# SCH_Mirge_Driving_Circuit_and_Power_2022.net
KiCad netlist of a schematic drawn in EasyEDA
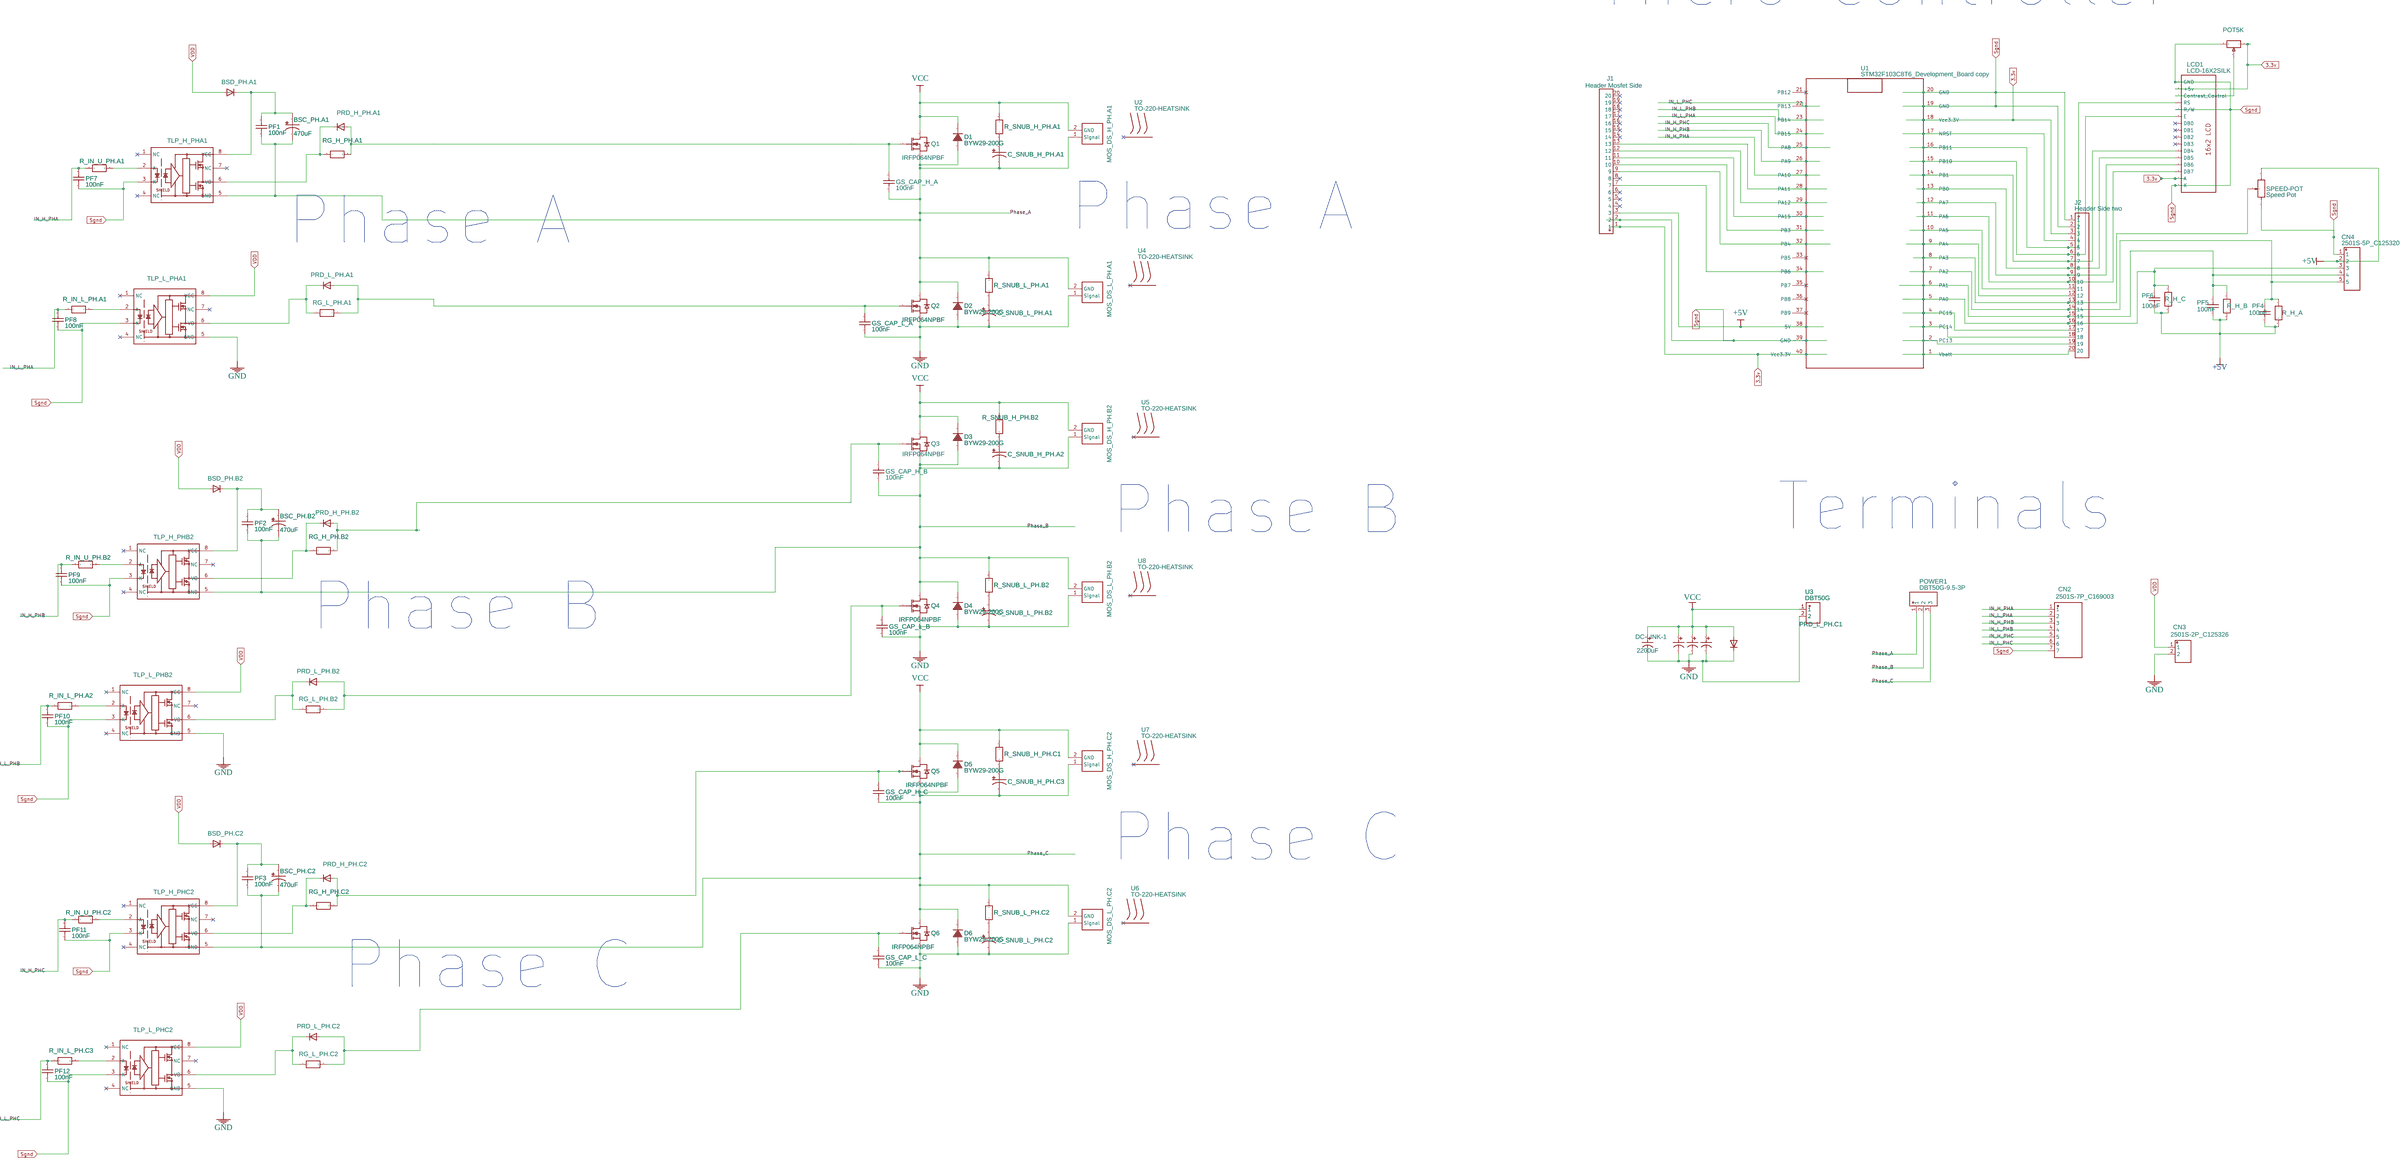
[diagram p0: schematic sheet]

(export (version "E")
  (design (tool "Eeschema 10.0.6"))
  (components
    (comp (ref "BSC_PH.A1")
      (value "470uF")
      (fields
        (field (name "BOM_Manufacturer Part") "RD1E477M1012MPA18P")
        (field (name "BOM_Supplier Part") "C160623")
      )
      (libsource (lib "") (part "RD1E477M1012MPA18P_4"))
    )
    (comp (ref "BSC_PH.B2")
      (value "470uF")
      (fields
        (field (name "BOM_Manufacturer Part") "RD1E477M1012MPA18P")
        (field (name "BOM_Supplier Part") "C160623")
      )
      (libsource (lib "") (part "RD1E477M1012MPA18P_2"))
    )
    (comp (ref "BSC_PH.C2")
      (value "470uF")
      (fields
        (field (name "BOM_Manufacturer Part") "RD1E477M1012MPA18P")
        (field (name "BOM_Supplier Part") "C160623")
      )
      (libsource (lib "") (part "RD1E477M1012MPA18P_3"))
    )
    (comp (ref "BSD_PH.A1") (value "DIODEDO-1N4148") (libsource (lib "") (part "DIODEDO-1N4148_2")))
    (comp (ref "BSD_PH.B2") (value "DIODEDO-1N4148") (libsource (lib "") (part "DIODEDO-1N4148_1")))
    (comp (ref "BSD_PH.C2") (value "DIODEDO-1N4148") (libsource (lib "") (part "DIODEDO-1N4148")))
    (comp (ref "CN2")
      (value "2501S-7P_C169003")
      (fields (field (name "BOM_Supplier Part") "C169003"))
      (libsource (lib "") (part "2501S-7P_C169003"))
    )
    (comp (ref "CN3")
      (value "2501S-2P_C125326")
      (fields (field (name "BOM_Manufacturer Part") "2501S-2P") (field (name "BOM_Supplier Part") "C125326"))
      (libsource (lib "") (part "2501S-2P_C125326"))
    )
    (comp (ref "CN4")
      (value "2501S-5P_C125320")
      (fields (field (name "BOM_Manufacturer Part") "2501S-5P") (field (name "BOM_Supplier Part") "C125320"))
      (libsource (lib "") (part "2501S-5P_C125320"))
    )
    (comp (ref "C_SNUB_H_PH.A1")
      (value "470uF")
      (fields
        (field (name "BOM_Manufacturer Part") "RD1E477M1012MPA18P")
        (field (name "BOM_Supplier Part") "C160623")
      )
      (libsource (lib "") (part "RD1E477M1012MPA18P_6"))
    )
    (comp (ref "C_SNUB_H_PH.A2")
      (value "470uF")
      (fields
        (field (name "BOM_Manufacturer Part") "RD1E477M1012MPA18P")
        (field (name "BOM_Supplier Part") "C160623")
      )
      (libsource (lib "") (part "RD1E477M1012MPA18P_1"))
    )
    (comp (ref "C_SNUB_H_PH.C3")
      (value "470uF")
      (fields
        (field (name "BOM_Manufacturer Part") "RD1E477M1012MPA18P")
        (field (name "BOM_Supplier Part") "C160623")
      )
      (libsource (lib "") (part "RD1E477M1012MPA18P"))
    )
    (comp (ref "C_SNUB_L_PH.A1")
      (value "470uF")
      (fields
        (field (name "BOM_Manufacturer Part") "RD1E477M1012MPA18P")
        (field (name "BOM_Supplier Part") "C160623")
      )
      (libsource (lib "") (part "RD1E477M1012MPA18P_8"))
    )
    (comp (ref "C_SNUB_L_PH.B2")
      (value "470uF")
      (fields
        (field (name "BOM_Manufacturer Part") "RD1E477M1012MPA18P")
        (field (name "BOM_Supplier Part") "C160623")
      )
      (libsource (lib "") (part "RD1E477M1012MPA18P_5"))
    )
    (comp (ref "C_SNUB_L_PH.C2")
      (value "470uF")
      (fields
        (field (name "BOM_Manufacturer Part") "RD1E477M1012MPA18P")
        (field (name "BOM_Supplier Part") "C160623")
      )
      (libsource (lib "") (part "RD1E477M1012MPA18P_7"))
    )
    (comp (ref "D1")
      (value "BYW29-200G")
      (fields (field (name "BOM_Supplier Part") "C232399"))
      (libsource (lib "") (part "BYW29-200G"))
    )
    (comp (ref "D2")
      (value "BYW29-200G")
      (fields (field (name "BOM_Supplier Part") "C232399"))
      (libsource (lib "") (part "BYW29-200G"))
    )
    (comp (ref "D3")
      (value "BYW29-200G")
      (fields (field (name "BOM_Supplier Part") "C232399"))
      (libsource (lib "") (part "BYW29-200G"))
    )
    (comp (ref "D4")
      (value "BYW29-200G")
      (fields (field (name "BOM_Supplier Part") "C232399"))
      (libsource (lib "") (part "BYW29-200G"))
    )
    (comp (ref "D5")
      (value "BYW29-200G")
      (fields (field (name "BOM_Supplier Part") "C232399"))
      (libsource (lib "") (part "BYW29-200G"))
    )
    (comp (ref "D6")
      (value "BYW29-200G")
      (fields (field (name "BOM_Supplier Part") "C232399"))
      (libsource (lib "") (part "BYW29-200G"))
    )
    (comp (ref "DC-LINK-1")
      (value "2200uF")
      (fields
        (field (name "BOM_Manufacturer Part") "2200uF 63V 18*30")
        (field (name "BOM_Supplier Part") "C47858")
      )
      (libsource (lib "") (part "2200uF 63V 18*30"))
    )
    (comp (ref "DC-LINK-2")
      (value "2200uF")
      (fields
        (field (name "BOM_Manufacturer Part") "2200uF 63V 18*30")
        (field (name "BOM_Supplier Part") "C47858")
      )
      (libsource (lib "") (part "2200uF 63V 18*30"))
    )
    (comp (ref "DC-LINK-3")
      (value "2200uF")
      (fields
        (field (name "BOM_Manufacturer Part") "2200uF 63V 18*30")
        (field (name "BOM_Supplier Part") "C47858")
      )
      (libsource (lib "") (part "2200uF 63V 18*30"))
    )
    (comp (ref "DC-LINK-4")
      (value "2200uF")
      (fields
        (field (name "BOM_Manufacturer Part") "2200uF 63V 18*30")
        (field (name "BOM_Supplier Part") "C47858")
      )
      (libsource (lib "") (part "2200uF 63V 18*30"))
    )
    (comp (ref "GS_CAP_H_A")
      (value "100nF")
      (fields
        (field (name "BOM_Manufacturer Part") "Calibration capacitor100nF（104）100V,5%")
        (field (name "BOM_Supplier Part") "C26609")
      )
      (libsource (lib "") (part "capacitor100nF（104）100V_3"))
    )
    (comp (ref "GS_CAP_H_B")
      (value "100nF")
      (fields
        (field (name "BOM_Manufacturer Part") "Calibration capacitor100nF（104）100V,5%")
        (field (name "BOM_Supplier Part") "C26609")
      )
      (libsource (lib "") (part "capacitor100nF（104）100V_4"))
    )
    (comp (ref "GS_CAP_H_C")
      (value "100nF")
      (fields
        (field (name "BOM_Manufacturer Part") "Calibration capacitor100nF（104）100V,5%")
        (field (name "BOM_Supplier Part") "C26609")
      )
      (libsource (lib "") (part "capacitor100nF（104）100V_7"))
    )
    (comp (ref "GS_CAP_L_A")
      (value "100nF")
      (fields
        (field (name "BOM_Manufacturer Part") "Calibration capacitor100nF（104）100V,5%")
        (field (name "BOM_Supplier Part") "C26609")
      )
      (libsource (lib "") (part "capacitor100nF（104）100V_2"))
    )
    (comp (ref "GS_CAP_L_B")
      (value "100nF")
      (fields
        (field (name "BOM_Manufacturer Part") "Calibration capacitor100nF（104）100V,5%")
        (field (name "BOM_Supplier Part") "C26609")
      )
      (libsource (lib "") (part "capacitor100nF（104）100V_6"))
    )
    (comp (ref "GS_CAP_L_C")
      (value "100nF")
      (fields
        (field (name "BOM_Manufacturer Part") "Calibration capacitor100nF（104）100V,5%")
        (field (name "BOM_Supplier Part") "C26609")
      )
      (libsource (lib "") (part "capacitor100nF（104）100V_5"))
    )
    (comp (ref "J1")
      (value "Header Mosfet Side")
      (fields
        (field (name "BOM_Manufacturer Part") "2.54mm 1*20PHeader")
        (field (name "BOM_Supplier Part") "C50981")
      )
      (libsource (lib "") (part "Header-Male-2.54_1x20_1"))
    )
    (comp (ref "J2")
      (value "Header Side two")
      (fields
        (field (name "BOM_Manufacturer Part") "2.54mm 1*20PHeader")
        (field (name "BOM_Supplier Part") "C50981")
      )
      (libsource (lib "") (part "Header-Male-2.54_1x20"))
    )
    (comp (ref "LCD1") (value "LCD-16X2SILK") (libsource (lib "") (part "LCD-16X2SILK")))
    (comp (ref "MOS_DS_H_PH.A1") (value "2 Pin Pinheader") (libsource (lib "") (part "2 Pin Pinheader_3")))
    (comp (ref "MOS_DS_H_PH.B2") (value "2 Pin Pinheader") (libsource (lib "") (part "2 Pin Pinheader_4")))
    (comp (ref "MOS_DS_H_PH.C2") (value "2 Pin Pinheader") (libsource (lib "") (part "2 Pin Pinheader")))
    (comp (ref "MOS_DS_L_PH.A1") (value "2 Pin Pinheader") (libsource (lib "") (part "2 Pin Pinheader_5")))
    (comp (ref "MOS_DS_L_PH.B2") (value "2 Pin Pinheader") (libsource (lib "") (part "2 Pin Pinheader_1")))
    (comp (ref "MOS_DS_L_PH.C2") (value "2 Pin Pinheader") (libsource (lib "") (part "2 Pin Pinheader_2")))
    (comp (ref "PF1")
      (value "100nF")
      (fields
        (field (name "BOM_Manufacturer Part") "Calibration capacitor100nF（104）100V,5%")
        (field (name "BOM_Supplier Part") "C26609")
      )
      (libsource (lib "") (part "capacitor100nF（104）100V_1"))
    )
    (comp (ref "PF2")
      (value "100nF")
      (fields
        (field (name "BOM_Manufacturer Part") "Calibration capacitor100nF（104）100V,5%")
        (field (name "BOM_Supplier Part") "C26609")
      )
      (libsource (lib "") (part "capacitor100nF（104）100V_1"))
    )
    (comp (ref "PF3")
      (value "100nF")
      (fields
        (field (name "BOM_Manufacturer Part") "Calibration capacitor100nF（104）100V,5%")
        (field (name "BOM_Supplier Part") "C26609")
      )
      (libsource (lib "") (part "capacitor100nF（104）100V_1"))
    )
    (comp (ref "PF4")
      (value "100nF")
      (fields
        (field (name "BOM_Manufacturer Part") "Calibration capacitor100nF（104）100V,5%")
        (field (name "BOM_Supplier Part") "C26609")
      )
      (libsource (lib "") (part "capacitor100nF（104）100V_1"))
    )
    (comp (ref "PF5")
      (value "100nF")
      (fields
        (field (name "BOM_Manufacturer Part") "Calibration capacitor100nF（104）100V,5%")
        (field (name "BOM_Supplier Part") "C26609")
      )
      (libsource (lib "") (part "capacitor100nF（104）100V"))
    )
    (comp (ref "PF6")
      (value "100nF")
      (fields
        (field (name "BOM_Manufacturer Part") "Calibration capacitor100nF（104）100V,5%")
        (field (name "BOM_Supplier Part") "C26609")
      )
      (libsource (lib "") (part "capacitor100nF（104）100V"))
    )
    (comp (ref "PF7")
      (value "100nF")
      (fields
        (field (name "BOM_Manufacturer Part") "Calibration capacitor100nF（104）100V,5%")
        (field (name "BOM_Supplier Part") "C26609")
      )
      (libsource (lib "") (part "capacitor100nF（104）100V_1"))
    )
    (comp (ref "PF8")
      (value "100nF")
      (fields
        (field (name "BOM_Manufacturer Part") "Calibration capacitor100nF（104）100V,5%")
        (field (name "BOM_Supplier Part") "C26609")
      )
      (libsource (lib "") (part "capacitor100nF（104）100V_1"))
    )
    (comp (ref "PF9")
      (value "100nF")
      (fields
        (field (name "BOM_Manufacturer Part") "Calibration capacitor100nF（104）100V,5%")
        (field (name "BOM_Supplier Part") "C26609")
      )
      (libsource (lib "") (part "capacitor100nF（104）100V_1"))
    )
    (comp (ref "PF10")
      (value "100nF")
      (fields
        (field (name "BOM_Manufacturer Part") "Calibration capacitor100nF（104）100V,5%")
        (field (name "BOM_Supplier Part") "C26609")
      )
      (libsource (lib "") (part "capacitor100nF（104）100V_1"))
    )
    (comp (ref "PF11")
      (value "100nF")
      (fields
        (field (name "BOM_Manufacturer Part") "Calibration capacitor100nF（104）100V,5%")
        (field (name "BOM_Supplier Part") "C26609")
      )
      (libsource (lib "") (part "capacitor100nF（104）100V_1"))
    )
    (comp (ref "PF12")
      (value "100nF")
      (fields
        (field (name "BOM_Manufacturer Part") "Calibration capacitor100nF（104）100V,5%")
        (field (name "BOM_Supplier Part") "C26609")
      )
      (libsource (lib "") (part "capacitor100nF（104）100V_1"))
    )
    (comp (ref "POT5K")
      (value "Potentiometer liegend Mini 6 mm")
      (fields (field (name "BOM_Supplier Part") "?"))
      (libsource (lib "") (part "Potentiometer liegend Mini 6 mm"))
    )
    (comp (ref "POWER1")
      (value "DBT50G-9.5-3P")
      (fields (field (name "BOM_Supplier Part") "C395959"))
      (libsource (lib "") (part "DBT50G-9.5-3P"))
    )
    (comp (ref "PRD_H_PH.A1") (value "DIODE COPY") (libsource (lib "") (part "DIODE COPY_3")))
    (comp (ref "PRD_H_PH.B2") (value "DIODE COPY") (libsource (lib "") (part "DIODE COPY_1")))
    (comp (ref "PRD_H_PH.C2") (value "DIODE COPY") (libsource (lib "") (part "DIODE COPY_6")))
    (comp (ref "PRD_L_PH.A1") (value "DIODE COPY") (libsource (lib "") (part "DIODE COPY_2")))
    (comp (ref "PRD_L_PH.B2") (value "DIODE COPY") (libsource (lib "") (part "DIODE COPY_5")))
    (comp (ref "PRD_L_PH.C1") (value "DIODE COPY") (libsource (lib "") (part "DIODE COPY")))
    (comp (ref "PRD_L_PH.C2") (value "DIODE COPY") (libsource (lib "") (part "DIODE COPY_4")))
    (comp (ref "Q1")
      (value "IRFP064NPBF")
      (fields (field (name "BOM_Supplier Part") "C9205"))
      (libsource (lib "") (part "IRFP064NPBF"))
    )
    (comp (ref "Q2")
      (value "IRFP064NPBF")
      (fields (field (name "BOM_Supplier Part") "C9205"))
      (libsource (lib "") (part "IRFP064NPBF"))
    )
    (comp (ref "Q3")
      (value "IRFP064NPBF")
      (fields (field (name "BOM_Supplier Part") "C9205"))
      (libsource (lib "") (part "IRFP064NPBF"))
    )
    (comp (ref "Q4")
      (value "IRFP064NPBF")
      (fields (field (name "BOM_Supplier Part") "C9205"))
      (libsource (lib "") (part "IRFP064NPBF"))
    )
    (comp (ref "Q5")
      (value "IRFP064NPBF")
      (fields (field (name "BOM_Supplier Part") "C9205"))
      (libsource (lib "") (part "IRFP064NPBF"))
    )
    (comp (ref "Q6")
      (value "IRFP064NPBF")
      (fields (field (name "BOM_Supplier Part") "C9205"))
      (libsource (lib "") (part "IRFP064NPBF"))
    )
    (comp (ref "RG_H_PH.A1") (value "220K 0.25W-TH") (libsource (lib "") (part "220K 0.25W-TH_13")))
    (comp (ref "RG_H_PH.B2") (value "220K 0.25W-TH") (libsource (lib "") (part "220K 0.25W-TH_14")))
    (comp (ref "RG_H_PH.C2") (value "220K 0.25W-TH") (libsource (lib "") (part "220K 0.25W-TH_9")))
    (comp (ref "RG_L_PH.A1") (value "220K 0.25W-TH") (libsource (lib "") (part "220K 0.25W-TH_12")))
    (comp (ref "RG_L_PH.B2") (value "220K 0.25W-TH") (libsource (lib "") (part "220K 0.25W-TH_7")))
    (comp (ref "RG_L_PH.C2") (value "220K 0.25W-TH") (libsource (lib "") (part "220K 0.25W-TH_17")))
    (comp (ref "R_H_A") (value "220K 0.25W-TH") (libsource (lib "") (part "220K 0.25W-TH_8")))
    (comp (ref "R_H_B") (value "220K 0.25W-TH") (libsource (lib "") (part "220K 0.25W-TH_19")))
    (comp (ref "R_H_C") (value "220K 0.25W-TH") (libsource (lib "") (part "220K 0.25W-TH_11")))
    (comp (ref "R_IN_L_PH.A1") (value "220K 0.25W-TH") (libsource (lib "") (part "220K 0.25W-TH_3")))
    (comp (ref "R_IN_L_PH.A2") (value "220K 0.25W-TH") (libsource (lib "") (part "220K 0.25W-TH_3")))
    (comp (ref "R_IN_L_PH.C3") (value "220K 0.25W-TH") (libsource (lib "") (part "220K 0.25W-TH_15")))
    (comp (ref "R_IN_U_PH.A1") (value "220K 0.25W-TH") (libsource (lib "") (part "220K 0.25W-TH_1")))
    (comp (ref "R_IN_U_PH.B2") (value "220K 0.25W-TH") (libsource (lib "") (part "220K 0.25W-TH_10")))
    (comp (ref "R_IN_U_PH.C2") (value "220K 0.25W-TH") (libsource (lib "") (part "220K 0.25W-TH_5")))
    (comp (ref "R_SNUB_H_PH.A1") (value "220K 0.25W-TH") (libsource (lib "") (part "220K 0.25W-TH_2")))
    (comp (ref "R_SNUB_H_PH.B2") (value "220K 0.25W-TH") (libsource (lib "") (part "220K 0.25W-TH_16")))
    (comp (ref "R_SNUB_H_PH.C1") (value "220K 0.25W-TH") (libsource (lib "") (part "220K 0.25W-TH_18")))
    (comp (ref "R_SNUB_L_PH.A1") (value "220K 0.25W-TH") (libsource (lib "") (part "220K 0.25W-TH_4")))
    (comp (ref "R_SNUB_L_PH.B2") (value "220K 0.25W-TH") (libsource (lib "") (part "220K 0.25W-TH")))
    (comp (ref "R_SNUB_L_PH.C2") (value "220K 0.25W-TH") (libsource (lib "") (part "220K 0.25W-TH_6")))
    (comp (ref "SPEED-POT") (value "Speed Pot") (libsource (lib "") (part "POTENTIOMETER")))
    (comp (ref "TLP_H_PHA1")
      (value "TLP350(F)")
      (fields (field (name "BOM_Supplier Part") "C50232"))
      (libsource (lib "") (part "TLP350(F)_5"))
    )
    (comp (ref "TLP_H_PHB2")
      (value "TLP350(F)")
      (fields (field (name "BOM_Supplier Part") "C50232"))
      (libsource (lib "") (part "TLP350(F)_4"))
    )
    (comp (ref "TLP_H_PHC2")
      (value "TLP350(F)")
      (fields (field (name "BOM_Supplier Part") "C50232"))
      (libsource (lib "") (part "TLP350(F)_1"))
    )
    (comp (ref "TLP_L_PHA1")
      (value "TLP350(F)")
      (fields (field (name "BOM_Supplier Part") "C50232"))
      (libsource (lib "") (part "TLP350(F)_3"))
    )
    (comp (ref "TLP_L_PHB2")
      (value "TLP350(F)")
      (fields (field (name "BOM_Supplier Part") "C50232"))
      (libsource (lib "") (part "TLP350(F)_2"))
    )
    (comp (ref "TLP_L_PHC2")
      (value "TLP350(F)")
      (fields (field (name "BOM_Supplier Part") "C50232"))
      (libsource (lib "") (part "TLP350(F)"))
    )
    (comp (ref "U1")
      (value "STM32F103C8T6_Development_Board copy")
      (fields (field (name "BOM_Manufacturer Part") "STM32Duino"))
      (libsource (lib "") (part "STM32F103C8T6_Development_Board copy"))
    )
    (comp (ref "U2") (value "TO-220-HEATSINK") (libsource (lib "") (part "TO-220-HEATSINK")))
    (comp (ref "U3")
      (value "DBT50G")
      (fields
        (field (name "BOM_Manufacturer Part") "DBT50G-9.5-2P")
        (field (name "BOM_Supplier Part") "C395958")
      )
      (libsource (lib "") (part "DBT50G-9.5-2P"))
    )
    (comp (ref "U4") (value "TO-220-HEATSINK") (libsource (lib "") (part "TO-220-HEATSINK")))
    (comp (ref "U5") (value "TO-220-HEATSINK") (libsource (lib "") (part "TO-220-HEATSINK")))
    (comp (ref "U6") (value "TO-220-HEATSINK") (libsource (lib "") (part "TO-220-HEATSINK")))
    (comp (ref "U7") (value "TO-220-HEATSINK") (libsource (lib "") (part "TO-220-HEATSINK")))
    (comp (ref "U8") (value "TO-220-HEATSINK") (libsource (lib "") (part "TO-220-HEATSINK")))
  )
  (nets
    (net (code "1") (name "+5V") (class "Default")
      (node (ref "CN4") (pin "2") (pinfunction "2_2") (pintype "unspecified"))
      (node (ref "J1") (pin "3") (pinfunction "3_3") (pintype "unspecified"))
      (node (ref "PF4") (pin "1") (pinfunction "1_1") (pintype "input"))
      (node (ref "PF5") (pin "2") (pinfunction "2_2") (pintype "input"))
      (node (ref "PF6") (pin "2") (pinfunction "2_2") (pintype "input"))
      (node (ref "R_H_A") (pin "2") (pinfunction "2_2") (pintype "input"))
      (node (ref "R_H_B") (pin "2") (pinfunction "2_2") (pintype "input"))
      (node (ref "R_H_C") (pin "2") (pinfunction "2_2") (pintype "input"))
      (node (ref "SPEED-POT") (pin "3") (pinfunction "3_3") (pintype "unspecified"))
      (node (ref "U1") (pin "38") (pinfunction "5V_38") (pintype "unspecified"))
    )
    (net (code "2") (name "/IN_H_PHA") (class "Default")
      (node (ref "CN2") (pin "1") (pinfunction "1_1") (pintype "unspecified"))
      (node (ref "PF7") (pin "2") (pinfunction "2_2") (pintype "input"))
      (node (ref "R_IN_U_PH.A1") (pin "1") (pinfunction "1_1") (pintype "input"))
      (node (ref "U1") (pin "27") (pinfunction "PA10_27") (pintype "unspecified"))
    )
    (net (code "3") (name "/IN_H_PHB") (class "Default")
      (node (ref "CN2") (pin "3") (pinfunction "3_3") (pintype "unspecified"))
      (node (ref "PF9") (pin "2") (pinfunction "2_2") (pintype "input"))
      (node (ref "R_IN_U_PH.B2") (pin "1") (pinfunction "1_1") (pintype "input"))
      (node (ref "U1") (pin "26") (pinfunction "PA9_26") (pintype "unspecified"))
    )
    (net (code "4") (name "/IN_H_PHC") (class "Default")
      (node (ref "CN2") (pin "5") (pinfunction "5_5") (pintype "unspecified"))
      (node (ref "PF11") (pin "2") (pinfunction "2_2") (pintype "input"))
      (node (ref "R_IN_U_PH.C2") (pin "1") (pinfunction "1_1") (pintype "input"))
      (node (ref "U1") (pin "25") (pinfunction "PA8_25") (pintype "unspecified"))
    )
    (net (code "5") (name "/IN_L_PHA") (class "Default")
      (node (ref "CN2") (pin "2") (pinfunction "2_2") (pintype "unspecified"))
      (node (ref "PF8") (pin "2") (pinfunction "2_2") (pintype "input"))
      (node (ref "R_IN_L_PH.A1") (pin "1") (pinfunction "1_1") (pintype "input"))
      (node (ref "U1") (pin "24") (pinfunction "PB15_24") (pintype "unspecified"))
    )
    (net (code "6") (name "/IN_L_PHB") (class "Default")
      (node (ref "CN2") (pin "4") (pinfunction "4_4") (pintype "unspecified"))
      (node (ref "PF10") (pin "2") (pinfunction "2_2") (pintype "input"))
      (node (ref "R_IN_L_PH.A2") (pin "1") (pinfunction "1_1") (pintype "input"))
      (node (ref "U1") (pin "23") (pinfunction "PB14_23") (pintype "unspecified"))
    )
    (net (code "7") (name "/IN_L_PHC") (class "Default")
      (node (ref "CN2") (pin "6") (pinfunction "6_6") (pintype "unspecified"))
      (node (ref "PF12") (pin "2") (pinfunction "2_2") (pintype "input"))
      (node (ref "R_IN_L_PH.C3") (pin "1") (pinfunction "1_1") (pintype "input"))
      (node (ref "U1") (pin "22") (pinfunction "PB13_22") (pintype "unspecified"))
    )
    (net (code "8") (name "/Phase_A") (class "Default")
      (node (ref "BSC_PH.A1") (pin "2") (pinfunction "2_2") (pintype "unspecified"))
      (node (ref "C_SNUB_H_PH.A1") (pin "2") (pinfunction "2_2") (pintype "unspecified"))
      (node (ref "D1") (pin "3") (pinfunction "A_3") (pintype "unspecified"))
      (node (ref "D2") (pin "1") (pinfunction "K_1") (pintype "unspecified"))
      (node (ref "GS_CAP_H_A") (pin "1") (pinfunction "1_1") (pintype "input"))
      (node (ref "MOS_DS_H_PH.A1") (pin "1") (pinfunction "Signal_1") (pintype "unspecified"))
      (node (ref "MOS_DS_L_PH.A1") (pin "2") (pinfunction "GND_2") (pintype "unspecified"))
      (node (ref "PF1") (pin "1") (pinfunction "1_1") (pintype "input"))
      (node (ref "POWER1") (pin "1") (pinfunction "1_1") (pintype "unspecified"))
      (node (ref "Q1") (pin "3") (pinfunction "S_3") (pintype "unspecified"))
      (node (ref "Q2") (pin "2") (pinfunction "D_2") (pintype "unspecified"))
      (node (ref "R_SNUB_L_PH.A1") (pin "2") (pinfunction "2_2") (pintype "input"))
      (node (ref "TLP_H_PHA1") (pin "5") (pinfunction "GND_5") (pintype "unspecified"))
    )
    (net (code "9") (name "/Phase_B") (class "Default")
      (node (ref "BSC_PH.B2") (pin "2") (pinfunction "2_2") (pintype "unspecified"))
      (node (ref "C_SNUB_H_PH.A2") (pin "2") (pinfunction "2_2") (pintype "unspecified"))
      (node (ref "D3") (pin "3") (pinfunction "A_3") (pintype "unspecified"))
      (node (ref "D4") (pin "1") (pinfunction "K_1") (pintype "unspecified"))
      (node (ref "GS_CAP_H_B") (pin "1") (pinfunction "1_1") (pintype "input"))
      (node (ref "MOS_DS_H_PH.B2") (pin "1") (pinfunction "Signal_1") (pintype "unspecified"))
      (node (ref "MOS_DS_L_PH.B2") (pin "2") (pinfunction "GND_2") (pintype "unspecified"))
      (node (ref "PF2") (pin "1") (pinfunction "1_1") (pintype "input"))
      (node (ref "POWER1") (pin "2") (pinfunction "2_2") (pintype "unspecified"))
      (node (ref "Q3") (pin "3") (pinfunction "S_3") (pintype "unspecified"))
      (node (ref "Q4") (pin "2") (pinfunction "D_2") (pintype "unspecified"))
      (node (ref "R_SNUB_L_PH.B2") (pin "2") (pinfunction "2_2") (pintype "input"))
      (node (ref "TLP_H_PHB2") (pin "5") (pinfunction "GND_5") (pintype "unspecified"))
    )
    (net (code "10") (name "/Phase_C") (class "Default")
      (node (ref "BSC_PH.C2") (pin "2") (pinfunction "2_2") (pintype "unspecified"))
      (node (ref "C_SNUB_H_PH.C3") (pin "2") (pinfunction "2_2") (pintype "unspecified"))
      (node (ref "D5") (pin "3") (pinfunction "A_3") (pintype "unspecified"))
      (node (ref "D6") (pin "1") (pinfunction "K_1") (pintype "unspecified"))
      (node (ref "GS_CAP_H_C") (pin "1") (pinfunction "1_1") (pintype "input"))
      (node (ref "MOS_DS_H_PH.C2") (pin "1") (pinfunction "Signal_1") (pintype "unspecified"))
      (node (ref "MOS_DS_L_PH.C2") (pin "2") (pinfunction "GND_2") (pintype "unspecified"))
      (node (ref "PF3") (pin "1") (pinfunction "1_1") (pintype "input"))
      (node (ref "POWER1") (pin "3") (pinfunction "3_3") (pintype "unspecified"))
      (node (ref "Q5") (pin "3") (pinfunction "S_3") (pintype "unspecified"))
      (node (ref "Q6") (pin "2") (pinfunction "D_2") (pintype "unspecified"))
      (node (ref "R_SNUB_L_PH.C2") (pin "2") (pinfunction "2_2") (pintype "input"))
      (node (ref "TLP_H_PHC2") (pin "5") (pinfunction "GND_5") (pintype "unspecified"))
    )
    (net (code "11") (name "3.3v") (class "Default")
      (node (ref "J1") (pin "1") (pinfunction "1_1") (pintype "unspecified"))
      (node (ref "J2") (pin "3") (pinfunction "3_3") (pintype "unspecified"))
      (node (ref "LCD1") (pin "15") (pinfunction "A_15") (pintype "bidirectional"))
      (node (ref "LCD1") (pin "2") (pinfunction "+5v_2") (pintype "bidirectional"))
      (node (ref "POT5K") (pin "1") (pinfunction "1_1") (pintype "input"))
      (node (ref "U1") (pin "18") (pinfunction "Vcc3.3V_18") (pintype "unspecified"))
      (node (ref "U1") (pin "40") (pinfunction "Vcc3.3V_40") (pintype "unspecified"))
    )
    (net (code "12") (name "GND") (class "Default")
      (node (ref "CN3") (pin "2") (pinfunction "2_2") (pintype "unspecified"))
      (node (ref "C_SNUB_L_PH.A1") (pin "2") (pinfunction "2_2") (pintype "unspecified"))
      (node (ref "C_SNUB_L_PH.B2") (pin "2") (pinfunction "2_2") (pintype "unspecified"))
      (node (ref "C_SNUB_L_PH.C2") (pin "2") (pinfunction "2_2") (pintype "unspecified"))
      (node (ref "D2") (pin "3") (pinfunction "A_3") (pintype "unspecified"))
      (node (ref "D4") (pin "3") (pinfunction "A_3") (pintype "unspecified"))
      (node (ref "D6") (pin "3") (pinfunction "A_3") (pintype "unspecified"))
      (node (ref "DC-LINK-1") (pin "2") (pinfunction "2_2") (pintype "input"))
      (node (ref "DC-LINK-2") (pin "2") (pinfunction "2_2") (pintype "input"))
      (node (ref "DC-LINK-3") (pin "2") (pinfunction "2_2") (pintype "input"))
      (node (ref "DC-LINK-4") (pin "2") (pinfunction "2_2") (pintype "input"))
      (node (ref "GS_CAP_L_A") (pin "1") (pinfunction "1_1") (pintype "input"))
      (node (ref "GS_CAP_L_B") (pin "1") (pinfunction "1_1") (pintype "input"))
      (node (ref "GS_CAP_L_C") (pin "1") (pinfunction "1_1") (pintype "input"))
      (node (ref "MOS_DS_L_PH.A1") (pin "1") (pinfunction "Signal_1") (pintype "unspecified"))
      (node (ref "MOS_DS_L_PH.B2") (pin "1") (pinfunction "Signal_1") (pintype "unspecified"))
      (node (ref "MOS_DS_L_PH.C2") (pin "1") (pinfunction "Signal_1") (pintype "unspecified"))
      (node (ref "PRD_L_PH.C1") (pin "C") (pinfunction "C_C") (pintype "unspecified"))
      (node (ref "Q2") (pin "3") (pinfunction "S_3") (pintype "unspecified"))
      (node (ref "Q4") (pin "3") (pinfunction "S_3") (pintype "unspecified"))
      (node (ref "Q6") (pin "3") (pinfunction "S_3") (pintype "unspecified"))
      (node (ref "TLP_L_PHA1") (pin "5") (pinfunction "GND_5") (pintype "unspecified"))
      (node (ref "TLP_L_PHB2") (pin "5") (pinfunction "GND_5") (pintype "unspecified"))
      (node (ref "TLP_L_PHC2") (pin "5") (pinfunction "GND_5") (pintype "unspecified"))
      (node (ref "U3") (pin "2") (pinfunction "2_2") (pintype "unspecified"))
    )
    (net (code "13") (name "Net-(C_SNUB_H_PH.A1-Pad1)") (class "Default")
      (node (ref "C_SNUB_H_PH.A1") (pin "1") (pinfunction "1_1") (pintype "unspecified"))
      (node (ref "R_SNUB_H_PH.A1") (pin "1") (pinfunction "1_1") (pintype "input"))
    )
    (net (code "14") (name "Net-(C_SNUB_H_PH.A2-Pad1)") (class "Default")
      (node (ref "C_SNUB_H_PH.A2") (pin "1") (pinfunction "1_1") (pintype "unspecified"))
      (node (ref "R_SNUB_H_PH.B2") (pin "1") (pinfunction "1_1") (pintype "input"))
    )
    (net (code "15") (name "Net-(C_SNUB_H_PH.C3-Pad1)") (class "Default")
      (node (ref "C_SNUB_H_PH.C3") (pin "1") (pinfunction "1_1") (pintype "unspecified"))
      (node (ref "R_SNUB_H_PH.C1") (pin "1") (pinfunction "1_1") (pintype "input"))
    )
    (net (code "16") (name "Net-(C_SNUB_L_PH.A1-Pad1)") (class "Default")
      (node (ref "C_SNUB_L_PH.A1") (pin "1") (pinfunction "1_1") (pintype "unspecified"))
      (node (ref "R_SNUB_L_PH.A1") (pin "1") (pinfunction "1_1") (pintype "input"))
    )
    (net (code "17") (name "Net-(C_SNUB_L_PH.B2-Pad1)") (class "Default")
      (node (ref "C_SNUB_L_PH.B2") (pin "1") (pinfunction "1_1") (pintype "unspecified"))
      (node (ref "R_SNUB_L_PH.B2") (pin "1") (pinfunction "1_1") (pintype "input"))
    )
    (net (code "18") (name "Net-(C_SNUB_L_PH.C2-Pad1)") (class "Default")
      (node (ref "C_SNUB_L_PH.C2") (pin "1") (pinfunction "1_1") (pintype "unspecified"))
      (node (ref "R_SNUB_L_PH.C2") (pin "1") (pinfunction "1_1") (pintype "input"))
    )
    (net (code "19") (name "Net-(LCD1-Contrast_Control)") (class "Default")
      (node (ref "LCD1") (pin "3") (pinfunction "Contrast_Control_3") (pintype "bidirectional"))
      (node (ref "POT5K") (pin "2") (pinfunction "2_2") (pintype "input"))
    )
    (net (code "20") (name "Net-(LCD1-DB4)") (class "Default")
      (node (ref "J2") (pin "7") (pinfunction "7_7") (pintype "unspecified"))
      (node (ref "LCD1") (pin "11") (pinfunction "DB4_11") (pintype "bidirectional"))
      (node (ref "U1") (pin "14") (pinfunction "PB1_14") (pintype "unspecified"))
    )
    (net (code "21") (name "Net-(LCD1-DB5)") (class "Default")
      (node (ref "J2") (pin "8") (pinfunction "8_8") (pintype "unspecified"))
      (node (ref "LCD1") (pin "12") (pinfunction "DB5_12") (pintype "bidirectional"))
      (node (ref "U1") (pin "13") (pinfunction "PB0_13") (pintype "unspecified"))
    )
    (net (code "22") (name "Net-(LCD1-DB6)") (class "Default")
      (node (ref "J2") (pin "9") (pinfunction "9_9") (pintype "unspecified"))
      (node (ref "LCD1") (pin "13") (pinfunction "DB6_13") (pintype "bidirectional"))
      (node (ref "U1") (pin "12") (pinfunction "PA7_12") (pintype "unspecified"))
    )
    (net (code "23") (name "Net-(LCD1-DB7)") (class "Default")
      (node (ref "J2") (pin "10") (pinfunction "10_10") (pintype "unspecified"))
      (node (ref "LCD1") (pin "14") (pinfunction "DB7_14") (pintype "bidirectional"))
      (node (ref "U1") (pin "11") (pinfunction "PA6_11") (pintype "unspecified"))
    )
    (net (code "24") (name "Net-(LCD1-E)") (class "Default")
      (node (ref "J2") (pin "6") (pinfunction "6_6") (pintype "unspecified"))
      (node (ref "LCD1") (pin "6") (pinfunction "E_6") (pintype "bidirectional"))
      (node (ref "U1") (pin "15") (pinfunction "PB10_15") (pintype "unspecified"))
    )
    (net (code "25") (name "Net-(LCD1-RS)") (class "Default")
      (node (ref "J2") (pin "5") (pinfunction "5_5") (pintype "unspecified"))
      (node (ref "LCD1") (pin "4") (pinfunction "RS_4") (pintype "bidirectional"))
      (node (ref "U1") (pin "16") (pinfunction "PB11_16") (pintype "unspecified"))
    )
    (net (code "26") (name "Net-(Q1-G)") (class "Default")
      (node (ref "GS_CAP_H_A") (pin "2") (pinfunction "2_2") (pintype "input"))
      (node (ref "PRD_H_PH.A1") (pin "A") (pinfunction "A_A") (pintype "unspecified"))
      (node (ref "Q1") (pin "1") (pinfunction "G_1") (pintype "unspecified"))
      (node (ref "RG_H_PH.A1") (pin "2") (pinfunction "2_2") (pintype "input"))
    )
    (net (code "27") (name "Net-(Q2-G)") (class "Default")
      (node (ref "GS_CAP_L_A") (pin "2") (pinfunction "2_2") (pintype "input"))
      (node (ref "PRD_L_PH.A1") (pin "A") (pinfunction "A_A") (pintype "unspecified"))
      (node (ref "Q2") (pin "1") (pinfunction "G_1") (pintype "unspecified"))
      (node (ref "RG_L_PH.A1") (pin "2") (pinfunction "2_2") (pintype "input"))
    )
    (net (code "28") (name "Net-(Q3-G)") (class "Default")
      (node (ref "GS_CAP_H_B") (pin "2") (pinfunction "2_2") (pintype "input"))
      (node (ref "PRD_H_PH.B2") (pin "A") (pinfunction "A_A") (pintype "unspecified"))
      (node (ref "Q3") (pin "1") (pinfunction "G_1") (pintype "unspecified"))
      (node (ref "RG_H_PH.B2") (pin "2") (pinfunction "2_2") (pintype "input"))
    )
    (net (code "29") (name "Net-(Q4-G)") (class "Default")
      (node (ref "GS_CAP_L_B") (pin "2") (pinfunction "2_2") (pintype "input"))
      (node (ref "PRD_L_PH.B2") (pin "A") (pinfunction "A_A") (pintype "unspecified"))
      (node (ref "Q4") (pin "1") (pinfunction "G_1") (pintype "unspecified"))
      (node (ref "RG_L_PH.B2") (pin "2") (pinfunction "2_2") (pintype "input"))
    )
    (net (code "30") (name "Net-(Q5-G)") (class "Default")
      (node (ref "GS_CAP_H_C") (pin "2") (pinfunction "2_2") (pintype "input"))
      (node (ref "PRD_H_PH.C2") (pin "A") (pinfunction "A_A") (pintype "unspecified"))
      (node (ref "Q5") (pin "1") (pinfunction "G_1") (pintype "unspecified"))
      (node (ref "RG_H_PH.C2") (pin "2") (pinfunction "2_2") (pintype "input"))
    )
    (net (code "31") (name "Net-(Q6-G)") (class "Default")
      (node (ref "GS_CAP_L_C") (pin "2") (pinfunction "2_2") (pintype "input"))
      (node (ref "PRD_L_PH.C2") (pin "A") (pinfunction "A_A") (pintype "unspecified"))
      (node (ref "Q6") (pin "1") (pinfunction "G_1") (pintype "unspecified"))
      (node (ref "RG_L_PH.C2") (pin "2") (pinfunction "2_2") (pintype "input"))
    )
    (net (code "32") (name "Net-(TLP_H_PHA1-A)") (class "Default")
      (node (ref "R_IN_U_PH.A1") (pin "2") (pinfunction "2_2") (pintype "input"))
      (node (ref "TLP_H_PHA1") (pin "2") (pinfunction "A_2") (pintype "unspecified"))
    )
    (net (code "33") (name "Net-(TLP_H_PHA1-VCC)") (class "Default")
      (node (ref "BSC_PH.A1") (pin "1") (pinfunction "1_1") (pintype "unspecified"))
      (node (ref "BSD_PH.A1") (pin "C") (pinfunction "C_C") (pintype "bidirectional"))
      (node (ref "PF1") (pin "2") (pinfunction "2_2") (pintype "input"))
      (node (ref "TLP_H_PHA1") (pin "8") (pinfunction "VCC_8") (pintype "unspecified"))
    )
    (net (code "34") (name "Net-(TLP_H_PHA1-VO)") (class "Default")
      (node (ref "PRD_H_PH.A1") (pin "C") (pinfunction "C_C") (pintype "unspecified"))
      (node (ref "RG_H_PH.A1") (pin "1") (pinfunction "1_1") (pintype "input"))
      (node (ref "TLP_H_PHA1") (pin "6") (pinfunction "VO_6") (pintype "unspecified"))
    )
    (net (code "35") (name "Net-(TLP_H_PHB2-A)") (class "Default")
      (node (ref "R_IN_U_PH.B2") (pin "2") (pinfunction "2_2") (pintype "input"))
      (node (ref "TLP_H_PHB2") (pin "2") (pinfunction "A_2") (pintype "unspecified"))
    )
    (net (code "36") (name "Net-(TLP_H_PHB2-VCC)") (class "Default")
      (node (ref "BSC_PH.B2") (pin "1") (pinfunction "1_1") (pintype "unspecified"))
      (node (ref "BSD_PH.B2") (pin "C") (pinfunction "C_C") (pintype "bidirectional"))
      (node (ref "PF2") (pin "2") (pinfunction "2_2") (pintype "input"))
      (node (ref "TLP_H_PHB2") (pin "8") (pinfunction "VCC_8") (pintype "unspecified"))
    )
    (net (code "37") (name "Net-(TLP_H_PHB2-VO)") (class "Default")
      (node (ref "PRD_H_PH.B2") (pin "C") (pinfunction "C_C") (pintype "unspecified"))
      (node (ref "RG_H_PH.B2") (pin "1") (pinfunction "1_1") (pintype "input"))
      (node (ref "TLP_H_PHB2") (pin "6") (pinfunction "VO_6") (pintype "unspecified"))
    )
    (net (code "38") (name "Net-(TLP_H_PHC2-A)") (class "Default")
      (node (ref "R_IN_U_PH.C2") (pin "2") (pinfunction "2_2") (pintype "input"))
      (node (ref "TLP_H_PHC2") (pin "2") (pinfunction "A_2") (pintype "unspecified"))
    )
    (net (code "39") (name "Net-(TLP_H_PHC2-VCC)") (class "Default")
      (node (ref "BSC_PH.C2") (pin "1") (pinfunction "1_1") (pintype "unspecified"))
      (node (ref "BSD_PH.C2") (pin "C") (pinfunction "C_C") (pintype "bidirectional"))
      (node (ref "PF3") (pin "2") (pinfunction "2_2") (pintype "input"))
      (node (ref "TLP_H_PHC2") (pin "8") (pinfunction "VCC_8") (pintype "unspecified"))
    )
    (net (code "40") (name "Net-(TLP_H_PHC2-VO)") (class "Default")
      (node (ref "PRD_H_PH.C2") (pin "C") (pinfunction "C_C") (pintype "unspecified"))
      (node (ref "RG_H_PH.C2") (pin "1") (pinfunction "1_1") (pintype "input"))
      (node (ref "TLP_H_PHC2") (pin "6") (pinfunction "VO_6") (pintype "unspecified"))
    )
    (net (code "41") (name "Net-(TLP_L_PHA1-A)") (class "Default")
      (node (ref "R_IN_L_PH.A1") (pin "2") (pinfunction "2_2") (pintype "input"))
      (node (ref "TLP_L_PHA1") (pin "2") (pinfunction "A_2") (pintype "unspecified"))
    )
    (net (code "42") (name "Net-(TLP_L_PHA1-VO)") (class "Default")
      (node (ref "PRD_L_PH.A1") (pin "C") (pinfunction "C_C") (pintype "unspecified"))
      (node (ref "RG_L_PH.A1") (pin "1") (pinfunction "1_1") (pintype "input"))
      (node (ref "TLP_L_PHA1") (pin "6") (pinfunction "VO_6") (pintype "unspecified"))
    )
    (net (code "43") (name "Net-(TLP_L_PHB2-A)") (class "Default")
      (node (ref "R_IN_L_PH.A2") (pin "2") (pinfunction "2_2") (pintype "input"))
      (node (ref "TLP_L_PHB2") (pin "2") (pinfunction "A_2") (pintype "unspecified"))
    )
    (net (code "44") (name "Net-(TLP_L_PHB2-VO)") (class "Default")
      (node (ref "PRD_L_PH.B2") (pin "C") (pinfunction "C_C") (pintype "unspecified"))
      (node (ref "RG_L_PH.B2") (pin "1") (pinfunction "1_1") (pintype "input"))
      (node (ref "TLP_L_PHB2") (pin "6") (pinfunction "VO_6") (pintype "unspecified"))
    )
    (net (code "45") (name "Net-(TLP_L_PHC2-A)") (class "Default")
      (node (ref "R_IN_L_PH.C3") (pin "2") (pinfunction "2_2") (pintype "input"))
      (node (ref "TLP_L_PHC2") (pin "2") (pinfunction "A_2") (pintype "unspecified"))
    )
    (net (code "46") (name "Net-(TLP_L_PHC2-VO)") (class "Default")
      (node (ref "PRD_L_PH.C2") (pin "C") (pinfunction "C_C") (pintype "unspecified"))
      (node (ref "RG_L_PH.C2") (pin "1") (pinfunction "1_1") (pintype "input"))
      (node (ref "TLP_L_PHC2") (pin "6") (pinfunction "VO_6") (pintype "unspecified"))
    )
    (net (code "47") (name "Net-(U1-NRST)") (class "Default")
      (node (ref "J2") (pin "4") (pinfunction "4_4") (pintype "unspecified"))
      (node (ref "U1") (pin "17") (pinfunction "NRST_17") (pintype "unspecified"))
    )
    (net (code "48") (name "Net-(U1-PA0)") (class "Default")
      (node (ref "CN4") (pin "3") (pinfunction "3_3") (pintype "unspecified"))
      (node (ref "J2") (pin "16") (pinfunction "16_16") (pintype "unspecified"))
      (node (ref "PF6") (pin "1") (pinfunction "1_1") (pintype "input"))
      (node (ref "R_H_C") (pin "1") (pinfunction "1_1") (pintype "input"))
      (node (ref "U1") (pin "5") (pinfunction "PA0_5") (pintype "unspecified"))
    )
    (net (code "49") (name "Net-(U1-PA1)") (class "Default")
      (node (ref "CN4") (pin "4") (pinfunction "4_4") (pintype "unspecified"))
      (node (ref "J2") (pin "15") (pinfunction "15_15") (pintype "unspecified"))
      (node (ref "PF5") (pin "1") (pinfunction "1_1") (pintype "input"))
      (node (ref "R_H_B") (pin "1") (pinfunction "1_1") (pintype "input"))
      (node (ref "U1") (pin "6") (pinfunction "PA1_6") (pintype "unspecified"))
    )
    (net (code "50") (name "Net-(U1-PA2)") (class "Default")
      (node (ref "CN4") (pin "5") (pinfunction "5_5") (pintype "unspecified"))
      (node (ref "J2") (pin "14") (pinfunction "14_14") (pintype "unspecified"))
      (node (ref "PF4") (pin "2") (pinfunction "2_2") (pintype "input"))
      (node (ref "R_H_A") (pin "1") (pinfunction "1_1") (pintype "input"))
      (node (ref "U1") (pin "7") (pinfunction "PA2_7") (pintype "unspecified"))
    )
    (net (code "51") (name "Net-(U1-PA3)") (class "Default")
      (node (ref "J2") (pin "13") (pinfunction "13_13") (pintype "unspecified"))
      (node (ref "SPEED-POT") (pin "2") (pinfunction "2_2") (pintype "unspecified"))
      (node (ref "U1") (pin "8") (pinfunction "PA3_8") (pintype "unspecified"))
    )
    (net (code "52") (name "Net-(U1-PA4)") (class "Default")
      (node (ref "J2") (pin "12") (pinfunction "12_12") (pintype "unspecified"))
      (node (ref "U1") (pin "9") (pinfunction "PA4_9") (pintype "unspecified"))
    )
    (net (code "53") (name "Net-(U1-PA5)") (class "Default")
      (node (ref "J2") (pin "11") (pinfunction "11_11") (pintype "unspecified"))
      (node (ref "U1") (pin "10") (pinfunction "PA5_10") (pintype "unspecified"))
    )
    (net (code "54") (name "Net-(U1-PA11)") (class "Default")
      (node (ref "J1") (pin "13") (pinfunction "13_13") (pintype "unspecified"))
      (node (ref "U1") (pin "28") (pinfunction "PA11_28") (pintype "unspecified"))
    )
    (net (code "55") (name "Net-(U1-PA12)") (class "Default")
      (node (ref "J1") (pin "12") (pinfunction "12_12") (pintype "unspecified"))
      (node (ref "U1") (pin "29") (pinfunction "PA12_29") (pintype "unspecified"))
    )
    (net (code "56") (name "Net-(U1-PA15)") (class "Default")
      (node (ref "J1") (pin "11") (pinfunction "11_11") (pintype "unspecified"))
      (node (ref "U1") (pin "30") (pinfunction "PA15_30") (pintype "unspecified"))
    )
    (net (code "57") (name "Net-(U1-PB3)") (class "Default")
      (node (ref "J1") (pin "10") (pinfunction "10_10") (pintype "unspecified"))
      (node (ref "U1") (pin "31") (pinfunction "PB3_31") (pintype "unspecified"))
    )
    (net (code "58") (name "Net-(U1-PB4)") (class "Default")
      (node (ref "J1") (pin "9") (pinfunction "9_9") (pintype "unspecified"))
      (node (ref "U1") (pin "32") (pinfunction "PB4_32") (pintype "unspecified"))
    )
    (net (code "59") (name "Net-(U1-PB6)") (class "Default")
      (node (ref "J1") (pin "7") (pinfunction "7_7") (pintype "unspecified"))
      (node (ref "U1") (pin "34") (pinfunction "PB6_34") (pintype "unspecified"))
    )
    (net (code "60") (name "Net-(U1-PC13)") (class "Default")
      (node (ref "J2") (pin "19") (pinfunction "19_19") (pintype "unspecified"))
      (node (ref "U1") (pin "2") (pinfunction "PC13_2") (pintype "unspecified"))
    )
    (net (code "61") (name "Net-(U1-PC14)") (class "Default")
      (node (ref "J2") (pin "18") (pinfunction "18_18") (pintype "unspecified"))
      (node (ref "U1") (pin "3") (pinfunction "PC14_3") (pintype "unspecified"))
    )
    (net (code "62") (name "Net-(U1-PC15)") (class "Default")
      (node (ref "J2") (pin "17") (pinfunction "17_17") (pintype "unspecified"))
      (node (ref "U1") (pin "4") (pinfunction "PC15_4") (pintype "unspecified"))
    )
    (net (code "63") (name "Net-(U1-Vbatt)") (class "Default")
      (node (ref "J2") (pin "20") (pinfunction "20_20") (pintype "unspecified"))
      (node (ref "U1") (pin "1") (pinfunction "Vbatt_1") (pintype "unspecified"))
    )
    (net (code "64") (name "Sgnd") (class "Default")
      (node (ref "CN2") (pin "7") (pinfunction "7_7") (pintype "unspecified"))
      (node (ref "CN4") (pin "1") (pinfunction "1_1") (pintype "unspecified"))
      (node (ref "J1") (pin "2") (pinfunction "2_2") (pintype "unspecified"))
      (node (ref "J2") (pin "1") (pinfunction "1_1") (pintype "unspecified"))
      (node (ref "J2") (pin "2") (pinfunction "2_2") (pintype "unspecified"))
      (node (ref "LCD1") (pin "1") (pinfunction "GND_1") (pintype "bidirectional"))
      (node (ref "LCD1") (pin "16") (pinfunction "K_16") (pintype "bidirectional"))
      (node (ref "LCD1") (pin "5") (pinfunction "R/W_5") (pintype "bidirectional"))
      (node (ref "PF10") (pin "1") (pinfunction "1_1") (pintype "input"))
      (node (ref "PF11") (pin "1") (pinfunction "1_1") (pintype "input"))
      (node (ref "PF12") (pin "1") (pinfunction "1_1") (pintype "input"))
      (node (ref "PF7") (pin "1") (pinfunction "1_1") (pintype "input"))
      (node (ref "PF8") (pin "1") (pinfunction "1_1") (pintype "input"))
      (node (ref "PF9") (pin "1") (pinfunction "1_1") (pintype "input"))
      (node (ref "POT5K") (pin "3") (pinfunction "3_3") (pintype "input"))
      (node (ref "SPEED-POT") (pin "1") (pinfunction "1_1") (pintype "unspecified"))
      (node (ref "TLP_H_PHA1") (pin "3") (pinfunction "K_3") (pintype "unspecified"))
      (node (ref "TLP_H_PHB2") (pin "3") (pinfunction "K_3") (pintype "unspecified"))
      (node (ref "TLP_H_PHC2") (pin "3") (pinfunction "K_3") (pintype "unspecified"))
      (node (ref "TLP_L_PHA1") (pin "3") (pinfunction "K_3") (pintype "unspecified"))
      (node (ref "TLP_L_PHB2") (pin "3") (pinfunction "K_3") (pintype "unspecified"))
      (node (ref "TLP_L_PHC2") (pin "3") (pinfunction "K_3") (pintype "unspecified"))
      (node (ref "U1") (pin "19") (pinfunction "GND_19") (pintype "unspecified"))
      (node (ref "U1") (pin "20") (pinfunction "GND_20") (pintype "unspecified"))
      (node (ref "U1") (pin "39") (pinfunction "GND_39") (pintype "unspecified"))
    )
    (net (code "65") (name "VCC") (class "Default")
      (node (ref "D1") (pin "1") (pinfunction "K_1") (pintype "unspecified"))
      (node (ref "D3") (pin "1") (pinfunction "K_1") (pintype "unspecified"))
      (node (ref "D5") (pin "1") (pinfunction "K_1") (pintype "unspecified"))
      (node (ref "DC-LINK-1") (pin "1") (pinfunction "1_1") (pintype "input"))
      (node (ref "DC-LINK-2") (pin "1") (pinfunction "1_1") (pintype "input"))
      (node (ref "DC-LINK-3") (pin "1") (pinfunction "1_1") (pintype "input"))
      (node (ref "DC-LINK-4") (pin "1") (pinfunction "1_1") (pintype "input"))
      (node (ref "MOS_DS_H_PH.A1") (pin "2") (pinfunction "GND_2") (pintype "unspecified"))
      (node (ref "MOS_DS_H_PH.B2") (pin "2") (pinfunction "GND_2") (pintype "unspecified"))
      (node (ref "MOS_DS_H_PH.C2") (pin "2") (pinfunction "GND_2") (pintype "unspecified"))
      (node (ref "PRD_L_PH.C1") (pin "A") (pinfunction "A_A") (pintype "unspecified"))
      (node (ref "Q1") (pin "2") (pinfunction "D_2") (pintype "unspecified"))
      (node (ref "Q3") (pin "2") (pinfunction "D_2") (pintype "unspecified"))
      (node (ref "Q5") (pin "2") (pinfunction "D_2") (pintype "unspecified"))
      (node (ref "R_SNUB_H_PH.A1") (pin "2") (pinfunction "2_2") (pintype "input"))
      (node (ref "R_SNUB_H_PH.B2") (pin "2") (pinfunction "2_2") (pintype "input"))
      (node (ref "R_SNUB_H_PH.C1") (pin "2") (pinfunction "2_2") (pintype "input"))
      (node (ref "U3") (pin "1") (pinfunction "1_1") (pintype "unspecified"))
    )
    (net (code "66") (name "VDD") (class "Default")
      (node (ref "BSD_PH.A1") (pin "A") (pinfunction "A_A") (pintype "bidirectional"))
      (node (ref "BSD_PH.B2") (pin "A") (pinfunction "A_A") (pintype "bidirectional"))
      (node (ref "BSD_PH.C2") (pin "A") (pinfunction "A_A") (pintype "bidirectional"))
      (node (ref "CN3") (pin "1") (pinfunction "1_1") (pintype "unspecified"))
      (node (ref "TLP_L_PHA1") (pin "8") (pinfunction "VCC_8") (pintype "unspecified"))
      (node (ref "TLP_L_PHB2") (pin "8") (pinfunction "VCC_8") (pintype "unspecified"))
      (node (ref "TLP_L_PHC2") (pin "8") (pinfunction "VCC_8") (pintype "unspecified"))
    )
    (net (code "67") (name "unconnected-(J1-Pad4)") (class "Default")
      (node (ref "J1") (pin "4") (pinfunction "4_4") (pintype "unspecified+no_connect"))
    )
    (net (code "68") (name "unconnected-(J1-Pad5)") (class "Default")
      (node (ref "J1") (pin "5") (pinfunction "5_5") (pintype "unspecified+no_connect"))
    )
    (net (code "69") (name "unconnected-(J1-Pad6)") (class "Default")
      (node (ref "J1") (pin "6") (pinfunction "6_6") (pintype "unspecified+no_connect"))
    )
    (net (code "70") (name "unconnected-(J1-Pad8)") (class "Default")
      (node (ref "J1") (pin "8") (pinfunction "8_8") (pintype "unspecified+no_connect"))
    )
    (net (code "71") (name "unconnected-(J1-Pad14)") (class "Default")
      (node (ref "J1") (pin "14") (pinfunction "14_14") (pintype "unspecified+no_connect"))
    )
    (net (code "72") (name "unconnected-(J1-Pad15)") (class "Default")
      (node (ref "J1") (pin "15") (pinfunction "15_15") (pintype "unspecified+no_connect"))
    )
    (net (code "73") (name "unconnected-(J1-Pad16)") (class "Default")
      (node (ref "J1") (pin "16") (pinfunction "16_16") (pintype "unspecified+no_connect"))
    )
    (net (code "74") (name "unconnected-(J1-Pad17)") (class "Default")
      (node (ref "J1") (pin "17") (pinfunction "17_17") (pintype "unspecified+no_connect"))
    )
    (net (code "75") (name "unconnected-(J1-Pad18)") (class "Default")
      (node (ref "J1") (pin "18") (pinfunction "18_18") (pintype "unspecified+no_connect"))
    )
    (net (code "76") (name "unconnected-(J1-Pad19)") (class "Default")
      (node (ref "J1") (pin "19") (pinfunction "19_19") (pintype "unspecified+no_connect"))
    )
    (net (code "77") (name "unconnected-(J1-Pad20)") (class "Default")
      (node (ref "J1") (pin "20") (pinfunction "20_20") (pintype "unspecified+no_connect"))
    )
    (net (code "78") (name "unconnected-(LCD1-DB0-Pad7)") (class "Default")
      (node (ref "LCD1") (pin "7") (pinfunction "DB0_7") (pintype "bidirectional+no_connect"))
    )
    (net (code "79") (name "unconnected-(LCD1-DB1-Pad8)") (class "Default")
      (node (ref "LCD1") (pin "8") (pinfunction "DB1_8") (pintype "bidirectional+no_connect"))
    )
    (net (code "80") (name "unconnected-(LCD1-DB2-Pad9)") (class "Default")
      (node (ref "LCD1") (pin "9") (pinfunction "DB2_9") (pintype "bidirectional+no_connect"))
    )
    (net (code "81") (name "unconnected-(LCD1-DB3-Pad10)") (class "Default")
      (node (ref "LCD1") (pin "10") (pinfunction "DB3_10") (pintype "bidirectional+no_connect"))
    )
    (net (code "82") (name "unconnected-(TLP_H_PHA1-NC-Pad1)") (class "Default")
      (node (ref "TLP_H_PHA1") (pin "1") (pinfunction "NC_1") (pintype "unspecified+no_connect"))
    )
    (net (code "83") (name "unconnected-(TLP_H_PHA1-NC-Pad4)") (class "Default")
      (node (ref "TLP_H_PHA1") (pin "4") (pinfunction "NC_4") (pintype "unspecified+no_connect"))
    )
    (net (code "84") (name "unconnected-(TLP_H_PHA1-NC-Pad7)") (class "Default")
      (node (ref "TLP_H_PHA1") (pin "7") (pinfunction "NC_7") (pintype "unspecified+no_connect"))
    )
    (net (code "85") (name "unconnected-(TLP_H_PHB2-NC-Pad1)") (class "Default")
      (node (ref "TLP_H_PHB2") (pin "1") (pinfunction "NC_1") (pintype "unspecified+no_connect"))
    )
    (net (code "86") (name "unconnected-(TLP_H_PHB2-NC-Pad4)") (class "Default")
      (node (ref "TLP_H_PHB2") (pin "4") (pinfunction "NC_4") (pintype "unspecified+no_connect"))
    )
    (net (code "87") (name "unconnected-(TLP_H_PHB2-NC-Pad7)") (class "Default")
      (node (ref "TLP_H_PHB2") (pin "7") (pinfunction "NC_7") (pintype "unspecified+no_connect"))
    )
    (net (code "88") (name "unconnected-(TLP_H_PHC2-NC-Pad1)") (class "Default")
      (node (ref "TLP_H_PHC2") (pin "1") (pinfunction "NC_1") (pintype "unspecified+no_connect"))
    )
    (net (code "89") (name "unconnected-(TLP_H_PHC2-NC-Pad4)") (class "Default")
      (node (ref "TLP_H_PHC2") (pin "4") (pinfunction "NC_4") (pintype "unspecified+no_connect"))
    )
    (net (code "90") (name "unconnected-(TLP_H_PHC2-NC-Pad7)") (class "Default")
      (node (ref "TLP_H_PHC2") (pin "7") (pinfunction "NC_7") (pintype "unspecified+no_connect"))
    )
    (net (code "91") (name "unconnected-(TLP_L_PHA1-NC-Pad1)") (class "Default")
      (node (ref "TLP_L_PHA1") (pin "1") (pinfunction "NC_1") (pintype "unspecified+no_connect"))
    )
    (net (code "92") (name "unconnected-(TLP_L_PHA1-NC-Pad4)") (class "Default")
      (node (ref "TLP_L_PHA1") (pin "4") (pinfunction "NC_4") (pintype "unspecified+no_connect"))
    )
    (net (code "93") (name "unconnected-(TLP_L_PHA1-NC-Pad7)") (class "Default")
      (node (ref "TLP_L_PHA1") (pin "7") (pinfunction "NC_7") (pintype "unspecified+no_connect"))
    )
    (net (code "94") (name "unconnected-(TLP_L_PHB2-NC-Pad1)") (class "Default")
      (node (ref "TLP_L_PHB2") (pin "1") (pinfunction "NC_1") (pintype "unspecified+no_connect"))
    )
    (net (code "95") (name "unconnected-(TLP_L_PHB2-NC-Pad4)") (class "Default")
      (node (ref "TLP_L_PHB2") (pin "4") (pinfunction "NC_4") (pintype "unspecified+no_connect"))
    )
    (net (code "96") (name "unconnected-(TLP_L_PHB2-NC-Pad7)") (class "Default")
      (node (ref "TLP_L_PHB2") (pin "7") (pinfunction "NC_7") (pintype "unspecified+no_connect"))
    )
    (net (code "97") (name "unconnected-(TLP_L_PHC2-NC-Pad1)") (class "Default")
      (node (ref "TLP_L_PHC2") (pin "1") (pinfunction "NC_1") (pintype "unspecified+no_connect"))
    )
    (net (code "98") (name "unconnected-(TLP_L_PHC2-NC-Pad4)") (class "Default")
      (node (ref "TLP_L_PHC2") (pin "4") (pinfunction "NC_4") (pintype "unspecified+no_connect"))
    )
    (net (code "99") (name "unconnected-(TLP_L_PHC2-NC-Pad7)") (class "Default")
      (node (ref "TLP_L_PHC2") (pin "7") (pinfunction "NC_7") (pintype "unspecified+no_connect"))
    )
    (net (code "100") (name "unconnected-(U1-PB5-Pad33)") (class "Default")
      (node (ref "U1") (pin "33") (pinfunction "PB5_33") (pintype "unspecified+no_connect"))
    )
    (net (code "101") (name "unconnected-(U1-PB7-Pad35)") (class "Default")
      (node (ref "U1") (pin "35") (pinfunction "PB7_35") (pintype "unspecified+no_connect"))
    )
    (net (code "102") (name "unconnected-(U1-PB8-Pad36)") (class "Default")
      (node (ref "U1") (pin "36") (pinfunction "PB8_36") (pintype "unspecified+no_connect"))
    )
    (net (code "103") (name "unconnected-(U1-PB9-Pad37)") (class "Default")
      (node (ref "U1") (pin "37") (pinfunction "PB9_37") (pintype "unspecified+no_connect"))
    )
    (net (code "104") (name "unconnected-(U1-PB12-Pad21)") (class "Default")
      (node (ref "U1") (pin "21") (pinfunction "PB12_21") (pintype "unspecified+no_connect"))
    )
  )
)
